# JD_BopIt_Schematic.net
KiCad netlist of a schematic drawn in Altium Designer
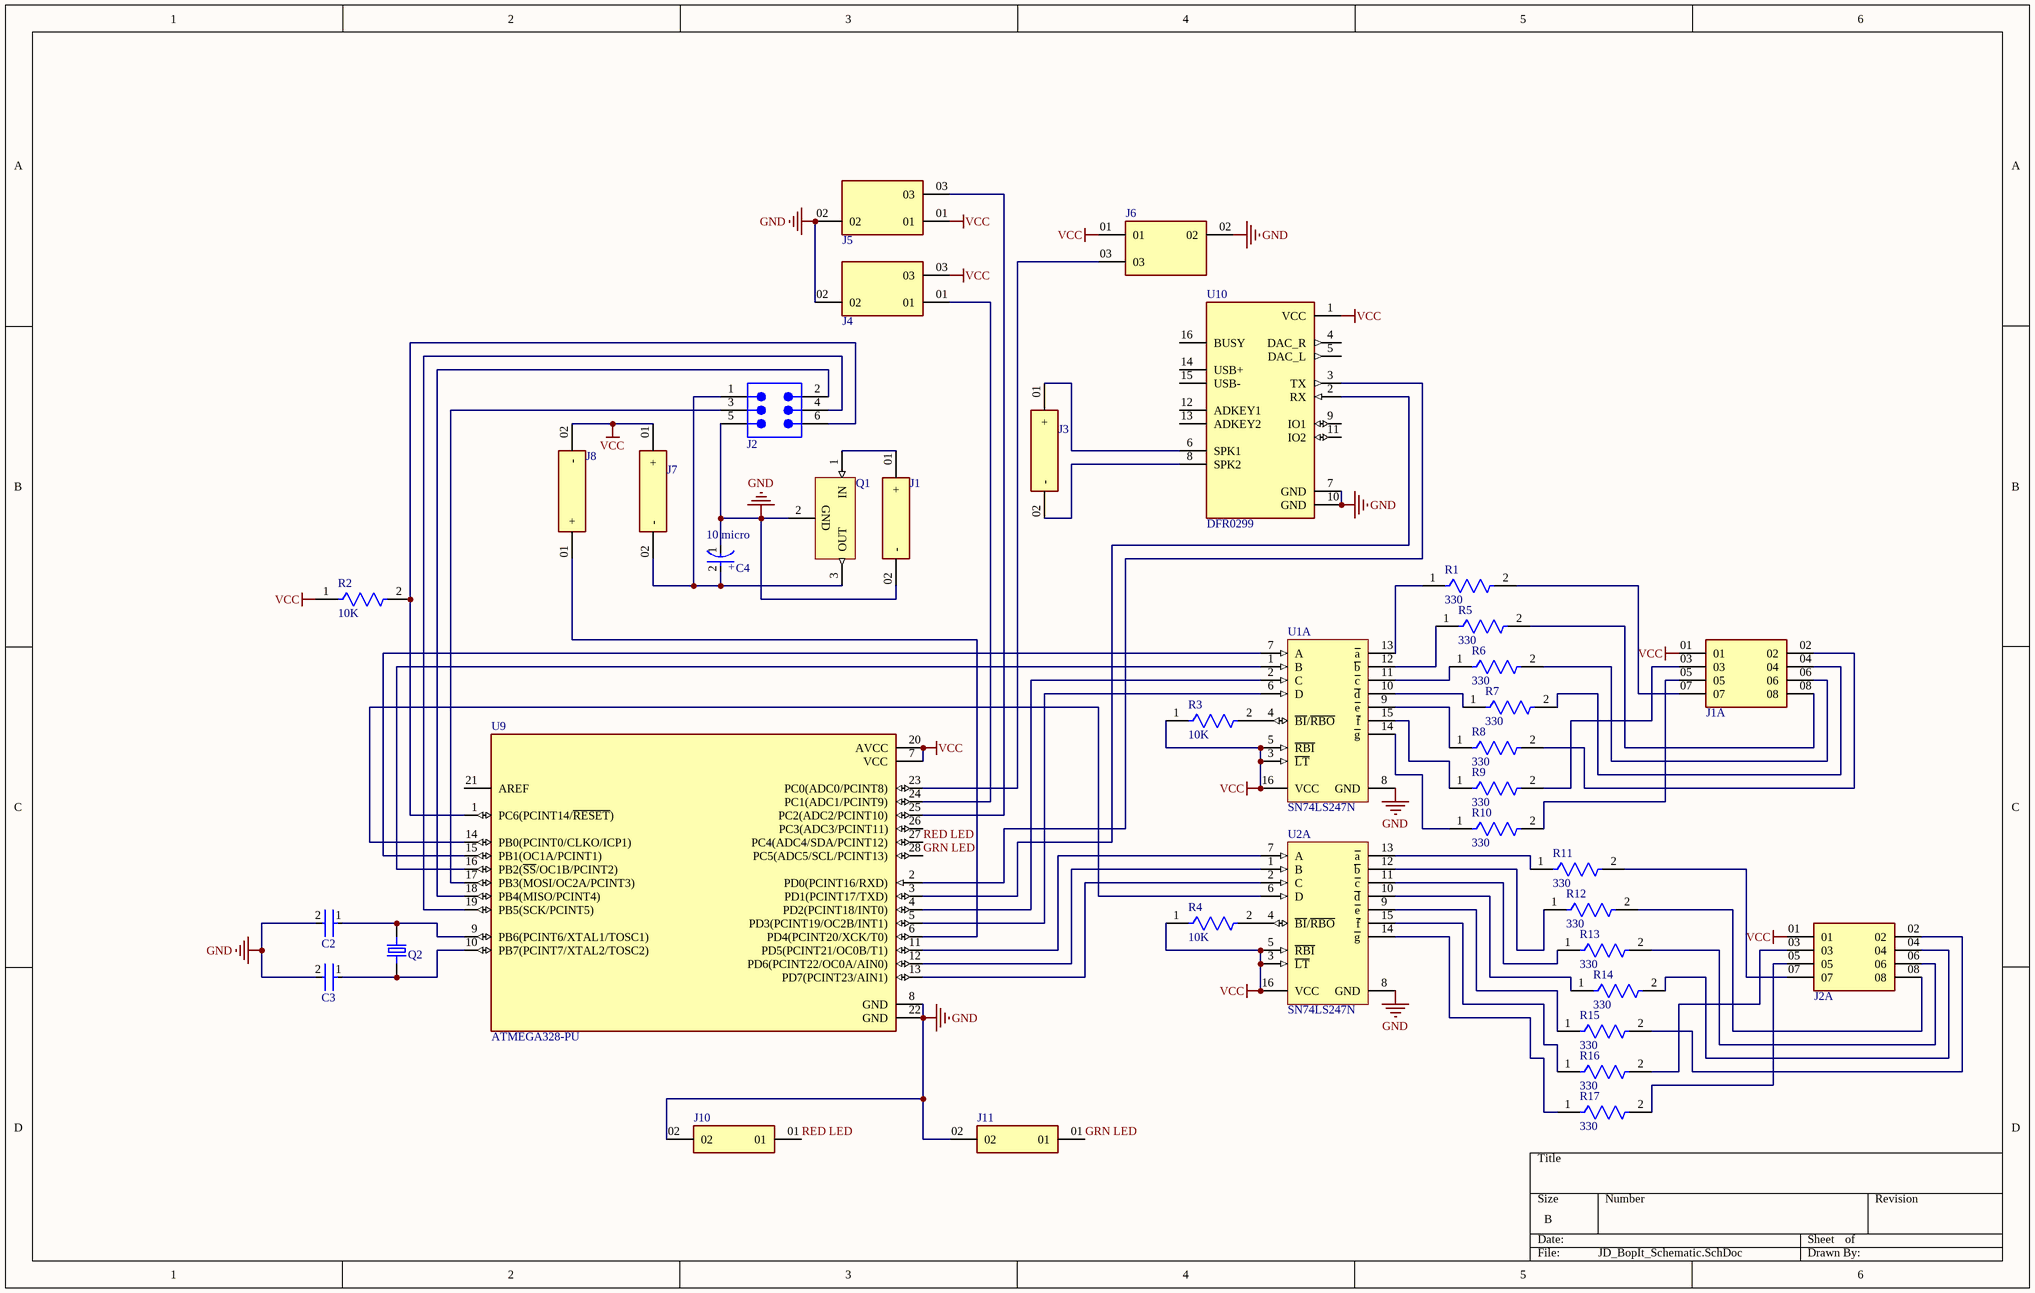
[diagram p0: JD_BopIt_Schematic.SchDoc]

(export (version "E")
  (design (tool "Eeschema 10.0.6"))
  (components
    (comp (ref "C2")
      (value "RCE5C2A220J0DBH03A")
      (footprint "FP-RCE0DB-MFG")
      (description "Cap Ceramic 22pF 100V C0G ±5% Radial 2.5mm +125°C Ammo Pack")
      (fields (field (name "VOLTAGE") "100V") (field (name "TOLERANCE") "5%"))
      (libsource (lib "Altium Content Vault") (part "b4654b650e69147ec39a6b967a45e02"))
    )
    (comp (ref "C3")
      (value "RCE5C2A220J0DBH03A")
      (footprint "FP-RCE0DB-MFG")
      (description "Cap Ceramic 22pF 100V C0G ±5% Radial 2.5mm +125°C Ammo Pack")
      (fields (field (name "VOLTAGE") "100V") (field (name "TOLERANCE") "5%"))
      (libsource (lib "Altium Content Vault") (part "b4654b650e69147ec39a6b967a45e02"))
    )
    (comp (ref "C4")
      (value "10 micro")
      (footprint "FP-173DW-MFG")
      (description "173D106X9025WWE3 173D Series 10 uF ±10% 25 V Axial Solid Electrolyte Tantalum Capacitor")
      (fields (field (name "TOLERANCE") "10%"))
      (libsource (lib "Altium Content Vault") (part "203bc49f2ac43e59fd269a8c329ed05"))
    )
    (comp (ref "J1")
      (value "MTSW-101-09-T-D-231-LL")
      (footprint "SAMTEC_MTSW-101-09-T-D-231-LL")
      (libsource (lib "MTSW-101-09-T-D-231-LL") (part "MTSW-101-09-T-D-231-LL"))
    )
    (comp (ref "J1A")
      (value "TSW-104-09-L-D")
      (footprint "SAMTEC_TSW-104-09-L-D")
      (libsource (lib "TSW-104-09-L-D") (part "TSW-104-09-L-D"))
    )
    (comp (ref "J2")
      (value "61200621621")
      (footprint "61200621621")
      (description "WR-BHD Male Box Header, THT Straight, pitch 2.54mm, 2 row, 6 pin")
      (fields (field (name "MANUFACTURER") "Wurth Elektronik"))
      (libsource (lib "Altium_WR-BHD_rev23a") (part "61200621621"))
    )
    (comp (ref "J2A")
      (value "TSW-104-09-L-D")
      (footprint "SAMTEC_TSW-104-09-L-D")
      (libsource (lib "TSW-104-09-L-D") (part "TSW-104-09-L-D"))
    )
    (comp (ref "J3")
      (value "MTSW-101-09-T-D-231-LL")
      (footprint "SAMTEC_MTSW-101-09-T-D-231-LL")
      (libsource (lib "MTSW-101-09-T-D-231-LL") (part "MTSW-101-09-T-D-231-LL"))
    )
    (comp (ref "J4")
      (value "HTSW-101-07-S-T")
      (footprint "SAMTEC_HTSW-101-07-S-T")
      (description "Connector Header Through Hole 3 position")
      (fields (field (name "MF") "Samtec"))
      (libsource (lib "HTSW-101-07-S-T") (part "HTSW-101-07-S-T"))
    )
    (comp (ref "J5")
      (value "HTSW-101-07-S-T")
      (footprint "SAMTEC_HTSW-101-07-S-T")
      (description "Connector Header Through Hole 3 position")
      (fields (field (name "MF") "Samtec"))
      (libsource (lib "HTSW-101-07-S-T") (part "HTSW-101-07-S-T"))
    )
    (comp (ref "J6")
      (value "HTSW-101-07-S-T")
      (footprint "SAMTEC_HTSW-101-07-S-T")
      (description "Connector Header Through Hole 3 position")
      (fields (field (name "MF") "Samtec"))
      (libsource (lib "") (part "HTSW-101-07-S-T_1"))
    )
    (comp (ref "J7")
      (value "MTSW-101-09-T-D-231-LL")
      (footprint "SAMTEC_MTSW-101-09-T-D-231-LL")
      (libsource (lib "MTSW-101-09-T-D-231-LL") (part "MTSW-101-09-T-D-231-LL"))
    )
    (comp (ref "J8")
      (value "MTSW-101-09-T-D-231-LL")
      (footprint "SAMTEC_MTSW-101-09-T-D-231-LL")
      (libsource (lib "") (part "MTSW-101-09-T-D-231-LL_2"))
    )
    (comp (ref "J10")
      (value "MTSW-101-09-T-D-231-LL")
      (footprint "SAMTEC_MTSW-101-09-T-D-231-LL")
      (libsource (lib "") (part "MTSW-101-09-T-D-231-LL_1"))
    )
    (comp (ref "J11")
      (value "MTSW-101-09-T-D-231-LL")
      (footprint "SAMTEC_MTSW-101-09-T-D-231-LL")
      (libsource (lib "") (part "MTSW-101-09-T-D-231-LL_1"))
    )
    (comp (ref "Q1")
      (value "LM7805CT")
      (footprint "FAIR-TO-220-3")
      (description "Positive Voltage Regulator, 5 V, 1 A, -40 to 125 degC, 3-Pin TO-220, RoHS, Tube")
      (fields (field (name "MANUFACTURER") "FairchildSemiconductor"))
      (libsource (lib "Altium Content Vault") (part "FAIR-LM7805CT-TO220-3"))
    )
    (comp (ref "Q2")
      (value "ECS-160-S-4")
      (footprint "XTAL_ECS-160-20-4X")
      (description "16 MHz Â±30ppm Crystal Series 40 Ohms HC-49/US")
      (fields (field (name "MF") "ECS Inc."))
      (libsource (lib "ECS-160-S-4") (part "ECS-160-S-4"))
    )
    (comp (ref "R1")
      (value "330")
      (footprint "FP-MBB0207-MFG")
      (description "RES 10K OHM 0.6W 1% AXIAL")
      (fields (field (name "TOLERANCE") "1%"))
      (libsource (lib "Altium Content Vault") (part "1029c3af85768c4190bb7ad29bc67b5"))
    )
    (comp (ref "R2")
      (value "10K")
      (footprint "FP-MBB0207-MFG")
      (description "RES 10K OHM 0.6W 1% AXIAL")
      (fields (field (name "TOLERANCE") "1%"))
      (libsource (lib "Altium Content Vault") (part "1029c3af85768c4190bb7ad29bc67b5"))
    )
    (comp (ref "R3")
      (value "10K")
      (footprint "FP-MBB0207-MFG")
      (description "RES 10K OHM 0.6W 1% AXIAL")
      (fields (field (name "TOLERANCE") "1%"))
      (libsource (lib "Altium Content Vault") (part "1029c3af85768c4190bb7ad29bc67b5"))
    )
    (comp (ref "R4")
      (value "10K")
      (footprint "FP-MBB0207-MFG")
      (description "RES 10K OHM 0.6W 1% AXIAL")
      (fields (field (name "TOLERANCE") "1%"))
      (libsource (lib "Altium Content Vault") (part "1029c3af85768c4190bb7ad29bc67b5"))
    )
    (comp (ref "R5")
      (value "330")
      (footprint "FP-MBB0207-MFG")
      (description "RES 10K OHM 0.6W 1% AXIAL")
      (fields (field (name "TOLERANCE") "1%"))
      (libsource (lib "Altium Content Vault") (part "1029c3af85768c4190bb7ad29bc67b5"))
    )
    (comp (ref "R6")
      (value "330")
      (footprint "FP-MBB0207-MFG")
      (description "RES 10K OHM 0.6W 1% AXIAL")
      (fields (field (name "TOLERANCE") "1%"))
      (libsource (lib "Altium Content Vault") (part "1029c3af85768c4190bb7ad29bc67b5"))
    )
    (comp (ref "R7")
      (value "330")
      (footprint "FP-MBB0207-MFG")
      (description "RES 10K OHM 0.6W 1% AXIAL")
      (fields (field (name "TOLERANCE") "1%"))
      (libsource (lib "Altium Content Vault") (part "1029c3af85768c4190bb7ad29bc67b5"))
    )
    (comp (ref "R8")
      (value "330")
      (footprint "FP-MBB0207-MFG")
      (description "RES 10K OHM 0.6W 1% AXIAL")
      (fields (field (name "TOLERANCE") "1%"))
      (libsource (lib "Altium Content Vault") (part "1029c3af85768c4190bb7ad29bc67b5"))
    )
    (comp (ref "R9")
      (value "330")
      (footprint "FP-MBB0207-MFG")
      (description "RES 10K OHM 0.6W 1% AXIAL")
      (fields (field (name "TOLERANCE") "1%"))
      (libsource (lib "Altium Content Vault") (part "1029c3af85768c4190bb7ad29bc67b5"))
    )
    (comp (ref "R10")
      (value "330")
      (footprint "FP-MBB0207-MFG")
      (description "RES 10K OHM 0.6W 1% AXIAL")
      (fields (field (name "TOLERANCE") "1%"))
      (libsource (lib "Altium Content Vault") (part "1029c3af85768c4190bb7ad29bc67b5"))
    )
    (comp (ref "R11")
      (value "330")
      (footprint "FP-MBB0207-MFG")
      (description "RES 10K OHM 0.6W 1% AXIAL")
      (fields (field (name "TOLERANCE") "1%"))
      (libsource (lib "Altium Content Vault") (part "1029c3af85768c4190bb7ad29bc67b5"))
    )
    (comp (ref "R12")
      (value "330")
      (footprint "FP-MBB0207-MFG")
      (description "RES 10K OHM 0.6W 1% AXIAL")
      (fields (field (name "TOLERANCE") "1%"))
      (libsource (lib "Altium Content Vault") (part "1029c3af85768c4190bb7ad29bc67b5"))
    )
    (comp (ref "R13")
      (value "330")
      (footprint "FP-MBB0207-MFG")
      (description "RES 10K OHM 0.6W 1% AXIAL")
      (fields (field (name "TOLERANCE") "1%"))
      (libsource (lib "Altium Content Vault") (part "1029c3af85768c4190bb7ad29bc67b5"))
    )
    (comp (ref "R14")
      (value "330")
      (footprint "FP-MBB0207-MFG")
      (description "RES 10K OHM 0.6W 1% AXIAL")
      (fields (field (name "TOLERANCE") "1%"))
      (libsource (lib "Altium Content Vault") (part "1029c3af85768c4190bb7ad29bc67b5"))
    )
    (comp (ref "R15")
      (value "330")
      (footprint "FP-MBB0207-MFG")
      (description "RES 10K OHM 0.6W 1% AXIAL")
      (fields (field (name "TOLERANCE") "1%"))
      (libsource (lib "Altium Content Vault") (part "1029c3af85768c4190bb7ad29bc67b5"))
    )
    (comp (ref "R16")
      (value "330")
      (footprint "FP-MBB0207-MFG")
      (description "RES 10K OHM 0.6W 1% AXIAL")
      (fields (field (name "TOLERANCE") "1%"))
      (libsource (lib "Altium Content Vault") (part "1029c3af85768c4190bb7ad29bc67b5"))
    )
    (comp (ref "R17")
      (value "330")
      (footprint "FP-MBB0207-MFG")
      (description "RES 10K OHM 0.6W 1% AXIAL")
      (fields (field (name "TOLERANCE") "1%"))
      (libsource (lib "Altium Content Vault") (part "1029c3af85768c4190bb7ad29bc67b5"))
    )
    (comp (ref "U1A")
      (value "SN74LS247N")
      (footprint "N0016A")
      (description "BCD-to-7-Segment Decoder / Driver, 4.75 to 5.25 V, 0 to 70 degC, 16-pin DIP (N16), Pb-Free (RoHS)")
      (fields (field (name "MANUFACTURER") "Texas Instruments"))
      (libsource (lib "Altium Content Vault") (part "TI-SNX4XX247-16"))
    )
    (comp (ref "U2A")
      (value "SN74LS247N")
      (footprint "N0016A")
      (description "BCD-to-7-Segment Decoder / Driver, 4.75 to 5.25 V, 0 to 70 degC, 16-pin DIP (N16), Pb-Free (RoHS)")
      (fields (field (name "MANUFACTURER") "Texas Instruments"))
      (libsource (lib "Altium Content Vault") (part "TI-SNX4XX247-16"))
    )
    (comp (ref "U9")
      (value "ATMEGA328-PU")
      (footprint "DIP787W46P254L3467H508Q28")
      (description "AVR AVRÂ® ATmega Microcontroller IC 8-Bit 20MHz 32KB (16K x 16) FLASH 28-PDIP")
      (fields (field (name "MF") "Microchip"))
      (libsource (lib "ATMEGA328-PU") (part "ATMEGA328-PU"))
    )
    (comp (ref "U10")
      (value "DFR0299")
      (footprint "MODULE_DFR0299")
      (description "- MP3 Player Audio Arduino Platform Evaluation Expansion Board")
      (fields (field (name "MF") "DFRobot"))
      (libsource (lib "DFR0299") (part "DFR0299"))
    )
  )
  (nets
    (net (code "1") (name "/GRN LED") (class "Default")
      (node (ref "J11") (pin "01") (pinfunction "01_01") (pintype "passive"))
      (node (ref "U9") (pin "28") (pinfunction "PC5(ADC5/SCL/PCINT13)_28") (pintype "bidirectional"))
    )
    (net (code "2") (name "/RED LED") (class "Default")
      (node (ref "J10") (pin "01") (pinfunction "01_01") (pintype "passive"))
      (node (ref "U9") (pin "27") (pinfunction "PC4(ADC4/SDA/PCINT12)_27") (pintype "bidirectional"))
    )
    (net (code "3") (name "GND") (class "Default")
      (node (ref "C2") (pin "2") (pinfunction "2_2") (pintype "passive"))
      (node (ref "C3") (pin "2") (pinfunction "2_2") (pintype "passive"))
      (node (ref "C4") (pin "1") (pinfunction "C_1") (pintype "passive"))
      (node (ref "J1") (pin "02") (pinfunction "-_02") (pintype "passive"))
      (node (ref "J10") (pin "02") (pinfunction "02_02") (pintype "passive"))
      (node (ref "J11") (pin "02") (pinfunction "02_02") (pintype "passive"))
      (node (ref "J2") (pin "5") (pinfunction "5_5") (pintype "passive"))
      (node (ref "J4") (pin "02") (pinfunction "02_02") (pintype "passive"))
      (node (ref "J5") (pin "02") (pinfunction "02_02") (pintype "passive"))
      (node (ref "J6") (pin "02") (pinfunction "02_02") (pintype "passive"))
      (node (ref "Q1") (pin "2") (pinfunction "GND_2") (pintype "power_in"))
      (node (ref "U10") (pin "10") (pinfunction "GND_10") (pintype "power_in"))
      (node (ref "U10") (pin "7") (pinfunction "GND_7") (pintype "power_in"))
      (node (ref "U1A") (pin "8") (pinfunction "GND_8") (pintype "power_in"))
      (node (ref "U2A") (pin "8") (pinfunction "GND_8") (pintype "power_in"))
      (node (ref "U9") (pin "22") (pinfunction "GND_22") (pintype "power_in"))
      (node (ref "U9") (pin "8") (pinfunction "GND_8") (pintype "power_in"))
    )
    (net (code "4") (name "Net-(C4-A)") (class "Default")
      (node (ref "C4") (pin "2") (pinfunction "A_2") (pintype "passive"))
      (node (ref "J2") (pin "1") (pinfunction "1_1") (pintype "passive"))
      (node (ref "J7") (pin "02") (pinfunction "-_02") (pintype "passive"))
      (node (ref "Q1") (pin "3") (pinfunction "OUT_3") (pintype "output"))
    )
    (net (code "5") (name "Net-(J1-+)") (class "Default")
      (node (ref "J1") (pin "01") (pinfunction "+_01") (pintype "passive"))
      (node (ref "Q1") (pin "1") (pinfunction "IN_1") (pintype "input"))
    )
    (net (code "6") (name "Net-(J1A-Pad02)") (class "Default")
      (node (ref "J1A") (pin "02") (pinfunction "02_02") (pintype "passive"))
      (node (ref "R8") (pin "2") (pinfunction "2_2") (pintype "passive"))
    )
    (net (code "7") (name "Net-(J1A-Pad03)") (class "Default")
      (node (ref "J1A") (pin "03") (pinfunction "03_03") (pintype "passive"))
      (node (ref "R9") (pin "2") (pinfunction "2_2") (pintype "passive"))
    )
    (net (code "8") (name "Net-(J1A-Pad04)") (class "Default")
      (node (ref "J1A") (pin "04") (pinfunction "04_04") (pintype "passive"))
      (node (ref "R7") (pin "2") (pinfunction "2_2") (pintype "passive"))
    )
    (net (code "9") (name "Net-(J1A-Pad05)") (class "Default")
      (node (ref "J1A") (pin "05") (pinfunction "05_05") (pintype "passive"))
      (node (ref "R10") (pin "2") (pinfunction "2_2") (pintype "passive"))
    )
    (net (code "10") (name "Net-(J1A-Pad06)") (class "Default")
      (node (ref "J1A") (pin "06") (pinfunction "06_06") (pintype "passive"))
      (node (ref "R6") (pin "2") (pinfunction "2_2") (pintype "passive"))
    )
    (net (code "11") (name "Net-(J1A-Pad07)") (class "Default")
      (node (ref "J1A") (pin "07") (pinfunction "07_07") (pintype "passive"))
      (node (ref "R1") (pin "2") (pinfunction "2_2") (pintype "passive"))
    )
    (net (code "12") (name "Net-(J1A-Pad08)") (class "Default")
      (node (ref "J1A") (pin "08") (pinfunction "08_08") (pintype "passive"))
      (node (ref "R5") (pin "2") (pinfunction "2_2") (pintype "passive"))
    )
    (net (code "13") (name "Net-(J2A-Pad02)") (class "Default")
      (node (ref "J2A") (pin "02") (pinfunction "02_02") (pintype "passive"))
      (node (ref "R15") (pin "2") (pinfunction "2_2") (pintype "passive"))
    )
    (net (code "14") (name "Net-(J2A-Pad03)") (class "Default")
      (node (ref "J2A") (pin "03") (pinfunction "03_03") (pintype "passive"))
      (node (ref "R16") (pin "2") (pinfunction "2_2") (pintype "passive"))
    )
    (net (code "15") (name "Net-(J2A-Pad04)") (class "Default")
      (node (ref "J2A") (pin "04") (pinfunction "04_04") (pintype "passive"))
      (node (ref "R14") (pin "2") (pinfunction "2_2") (pintype "passive"))
    )
    (net (code "16") (name "Net-(J2A-Pad05)") (class "Default")
      (node (ref "J2A") (pin "05") (pinfunction "05_05") (pintype "passive"))
      (node (ref "R17") (pin "2") (pinfunction "2_2") (pintype "passive"))
    )
    (net (code "17") (name "Net-(J2A-Pad06)") (class "Default")
      (node (ref "J2A") (pin "06") (pinfunction "06_06") (pintype "passive"))
      (node (ref "R13") (pin "2") (pinfunction "2_2") (pintype "passive"))
    )
    (net (code "18") (name "Net-(J2A-Pad07)") (class "Default")
      (node (ref "J2A") (pin "07") (pinfunction "07_07") (pintype "passive"))
      (node (ref "R11") (pin "2") (pinfunction "2_2") (pintype "passive"))
    )
    (net (code "19") (name "Net-(J2A-Pad08)") (class "Default")
      (node (ref "J2A") (pin "08") (pinfunction "08_08") (pintype "passive"))
      (node (ref "R12") (pin "2") (pinfunction "2_2") (pintype "passive"))
    )
    (net (code "20") (name "Net-(J3-+)") (class "Default")
      (node (ref "J3") (pin "01") (pinfunction "+_01") (pintype "passive"))
      (node (ref "U10") (pin "6") (pinfunction "SPK1_6") (pintype "passive"))
    )
    (net (code "21") (name "Net-(J3--)") (class "Default")
      (node (ref "J3") (pin "02") (pinfunction "-_02") (pintype "passive"))
      (node (ref "U10") (pin "8") (pinfunction "SPK2_8") (pintype "passive"))
    )
    (net (code "22") (name "Net-(J8-+)") (class "Default")
      (node (ref "J8") (pin "01") (pinfunction "+_01") (pintype "passive"))
      (node (ref "U9") (pin "6") (pinfunction "PD4(PCINT20/XCK/T0)_6") (pintype "bidirectional"))
    )
    (net (code "23") (name "Net-(U1A-A)") (class "Default")
      (node (ref "U1A") (pin "7") (pinfunction "A_7") (pintype "input"))
      (node (ref "U9") (pin "15") (pinfunction "PB1(OC1A/PCINT1)_15") (pintype "bidirectional"))
    )
    (net (code "24") (name "Net-(U1A-B)") (class "Default")
      (node (ref "U1A") (pin "1") (pinfunction "B_1") (pintype "input"))
      (node (ref "U9") (pin "16") (pinfunction "PB2(~{SS}/OC1B/PCINT2)_16") (pintype "bidirectional"))
    )
    (net (code "25") (name "Net-(U1A-C)") (class "Default")
      (node (ref "U1A") (pin "2") (pinfunction "C_2") (pintype "input"))
      (node (ref "U9") (pin "4") (pinfunction "PD2(PCINT18/INT0)_4") (pintype "bidirectional"))
    )
    (net (code "26") (name "Net-(U1A-D)") (class "Default")
      (node (ref "U1A") (pin "6") (pinfunction "D_6") (pintype "input"))
      (node (ref "U9") (pin "5") (pinfunction "PD3(PCINT19/OC2B/INT1)_5") (pintype "bidirectional"))
    )
    (net (code "27") (name "Net-(U1A-~{BI}{slash}~{RBO})") (class "Default")
      (node (ref "R3") (pin "2") (pinfunction "2_2") (pintype "passive"))
      (node (ref "U1A") (pin "4") (pinfunction "~{BI}/~{RBO}_4") (pintype "bidirectional"))
    )
    (net (code "28") (name "Net-(U1A-~{a})") (class "Default")
      (node (ref "R1") (pin "1") (pinfunction "1_1") (pintype "passive"))
      (node (ref "U1A") (pin "13") (pinfunction "~{a}_13") (pintype "open_collector"))
    )
    (net (code "29") (name "Net-(U1A-~{b})") (class "Default")
      (node (ref "R5") (pin "1") (pinfunction "1_1") (pintype "passive"))
      (node (ref "U1A") (pin "12") (pinfunction "~{b}_12") (pintype "open_collector"))
    )
    (net (code "30") (name "Net-(U1A-~{c})") (class "Default")
      (node (ref "R6") (pin "1") (pinfunction "1_1") (pintype "passive"))
      (node (ref "U1A") (pin "11") (pinfunction "~{c}_11") (pintype "open_collector"))
    )
    (net (code "31") (name "Net-(U1A-~{d})") (class "Default")
      (node (ref "R7") (pin "1") (pinfunction "1_1") (pintype "passive"))
      (node (ref "U1A") (pin "10") (pinfunction "~{d}_10") (pintype "open_collector"))
    )
    (net (code "32") (name "Net-(U1A-~{e})") (class "Default")
      (node (ref "R8") (pin "1") (pinfunction "1_1") (pintype "passive"))
      (node (ref "U1A") (pin "9") (pinfunction "~{e}_9") (pintype "open_collector"))
    )
    (net (code "33") (name "Net-(U1A-~{f})") (class "Default")
      (node (ref "R9") (pin "1") (pinfunction "1_1") (pintype "passive"))
      (node (ref "U1A") (pin "15") (pinfunction "~{f}_15") (pintype "open_collector"))
    )
    (net (code "34") (name "Net-(U1A-~{g})") (class "Default")
      (node (ref "R10") (pin "1") (pinfunction "1_1") (pintype "passive"))
      (node (ref "U1A") (pin "14") (pinfunction "~{g}_14") (pintype "open_collector"))
    )
    (net (code "35") (name "Net-(U2A-A)") (class "Default")
      (node (ref "U2A") (pin "7") (pinfunction "A_7") (pintype "input"))
      (node (ref "U9") (pin "11") (pinfunction "PD5(PCINT21/OC0B/T1)_11") (pintype "bidirectional"))
    )
    (net (code "36") (name "Net-(U2A-B)") (class "Default")
      (node (ref "U2A") (pin "1") (pinfunction "B_1") (pintype "input"))
      (node (ref "U9") (pin "12") (pinfunction "PD6(PCINT22/OC0A/AIN0)_12") (pintype "bidirectional"))
    )
    (net (code "37") (name "Net-(U2A-C)") (class "Default")
      (node (ref "U2A") (pin "2") (pinfunction "C_2") (pintype "input"))
      (node (ref "U9") (pin "13") (pinfunction "PD7(PCINT23/AIN1)_13") (pintype "bidirectional"))
    )
    (net (code "38") (name "Net-(U2A-D)") (class "Default")
      (node (ref "U2A") (pin "6") (pinfunction "D_6") (pintype "input"))
      (node (ref "U9") (pin "14") (pinfunction "PB0(PCINT0/CLKO/ICP1)_14") (pintype "bidirectional"))
    )
    (net (code "39") (name "Net-(U2A-~{BI}{slash}~{RBO})") (class "Default")
      (node (ref "R4") (pin "2") (pinfunction "2_2") (pintype "passive"))
      (node (ref "U2A") (pin "4") (pinfunction "~{BI}/~{RBO}_4") (pintype "bidirectional"))
    )
    (net (code "40") (name "Net-(U2A-~{a})") (class "Default")
      (node (ref "R11") (pin "1") (pinfunction "1_1") (pintype "passive"))
      (node (ref "U2A") (pin "13") (pinfunction "~{a}_13") (pintype "open_collector"))
    )
    (net (code "41") (name "Net-(U2A-~{b})") (class "Default")
      (node (ref "R12") (pin "1") (pinfunction "1_1") (pintype "passive"))
      (node (ref "U2A") (pin "12") (pinfunction "~{b}_12") (pintype "open_collector"))
    )
    (net (code "42") (name "Net-(U2A-~{c})") (class "Default")
      (node (ref "R13") (pin "1") (pinfunction "1_1") (pintype "passive"))
      (node (ref "U2A") (pin "11") (pinfunction "~{c}_11") (pintype "open_collector"))
    )
    (net (code "43") (name "Net-(U2A-~{d})") (class "Default")
      (node (ref "R14") (pin "1") (pinfunction "1_1") (pintype "passive"))
      (node (ref "U2A") (pin "10") (pinfunction "~{d}_10") (pintype "open_collector"))
    )
    (net (code "44") (name "Net-(U2A-~{e})") (class "Default")
      (node (ref "R15") (pin "1") (pinfunction "1_1") (pintype "passive"))
      (node (ref "U2A") (pin "9") (pinfunction "~{e}_9") (pintype "open_collector"))
    )
    (net (code "45") (name "Net-(U2A-~{f})") (class "Default")
      (node (ref "R16") (pin "1") (pinfunction "1_1") (pintype "passive"))
      (node (ref "U2A") (pin "15") (pinfunction "~{f}_15") (pintype "open_collector"))
    )
    (net (code "46") (name "Net-(U2A-~{g})") (class "Default")
      (node (ref "R17") (pin "1") (pinfunction "1_1") (pintype "passive"))
      (node (ref "U2A") (pin "14") (pinfunction "~{g}_14") (pintype "open_collector"))
    )
    (net (code "47") (name "Net-(U9-PB3(MOSI{slash}OC2A{slash}PCINT3))") (class "Default")
      (node (ref "J2") (pin "3") (pinfunction "3_3") (pintype "passive"))
      (node (ref "U9") (pin "17") (pinfunction "PB3(MOSI/OC2A/PCINT3)_17") (pintype "bidirectional"))
    )
    (net (code "48") (name "Net-(U9-PB4(MISO{slash}PCINT4))") (class "Default")
      (node (ref "J2") (pin "2") (pinfunction "2_2") (pintype "passive"))
      (node (ref "U9") (pin "18") (pinfunction "PB4(MISO/PCINT4)_18") (pintype "bidirectional"))
    )
    (net (code "49") (name "Net-(U9-PB5(SCK{slash}PCINT5))") (class "Default")
      (node (ref "J2") (pin "4") (pinfunction "4_4") (pintype "passive"))
      (node (ref "U9") (pin "19") (pinfunction "PB5(SCK/PCINT5)_19") (pintype "bidirectional"))
    )
    (net (code "50") (name "Net-(U9-PB6(PCINT6{slash}XTAL1{slash}TOSC1))") (class "Default")
      (node (ref "C2") (pin "1") (pinfunction "1_1") (pintype "passive"))
      (node (ref "Q2") (pin "2") (pinfunction "2_2") (pintype "passive"))
      (node (ref "U9") (pin "9") (pinfunction "PB6(PCINT6/XTAL1/TOSC1)_9") (pintype "bidirectional"))
    )
    (net (code "51") (name "Net-(U9-PB7(PCINT7{slash}XTAL2{slash}TOSC2))") (class "Default")
      (node (ref "C3") (pin "1") (pinfunction "1_1") (pintype "passive"))
      (node (ref "Q2") (pin "1") (pinfunction "1_1") (pintype "passive"))
      (node (ref "U9") (pin "10") (pinfunction "PB7(PCINT7/XTAL2/TOSC2)_10") (pintype "bidirectional"))
    )
    (net (code "52") (name "Net-(U9-PC0(ADC0{slash}PCINT8))") (class "Default")
      (node (ref "J6") (pin "03") (pinfunction "03_03") (pintype "passive"))
      (node (ref "U9") (pin "23") (pinfunction "PC0(ADC0/PCINT8)_23") (pintype "bidirectional"))
    )
    (net (code "53") (name "Net-(U9-PC1(ADC1{slash}PCINT9))") (class "Default")
      (node (ref "J4") (pin "01") (pinfunction "01_01") (pintype "passive"))
      (node (ref "U9") (pin "24") (pinfunction "PC1(ADC1/PCINT9)_24") (pintype "bidirectional"))
    )
    (net (code "54") (name "Net-(U9-PC2(ADC2{slash}PCINT10))") (class "Default")
      (node (ref "J5") (pin "03") (pinfunction "03_03") (pintype "passive"))
      (node (ref "U9") (pin "25") (pinfunction "PC2(ADC2/PCINT10)_25") (pintype "bidirectional"))
    )
    (net (code "55") (name "Net-(U9-PC6(PCINT14{slash}~{RESET}))") (class "Default")
      (node (ref "J2") (pin "6") (pinfunction "6_6") (pintype "passive"))
      (node (ref "R2") (pin "2") (pinfunction "2_2") (pintype "passive"))
      (node (ref "U9") (pin "1") (pinfunction "PC6(PCINT14/~{RESET})_1") (pintype "bidirectional"))
    )
    (net (code "56") (name "Net-(U10-RX)") (class "Default")
      (node (ref "U10") (pin "2") (pinfunction "RX_2") (pintype "input"))
      (node (ref "U9") (pin "3") (pinfunction "PD1(PCINT17/TXD)_3") (pintype "bidirectional"))
    )
    (net (code "57") (name "Net-(U10-TX)") (class "Default")
      (node (ref "U10") (pin "3") (pinfunction "TX_3") (pintype "output"))
      (node (ref "U9") (pin "2") (pinfunction "PD0(PCINT16/RXD)_2") (pintype "input"))
    )
    (net (code "58") (name "VCC") (class "Default")
      (node (ref "J1A") (pin "01") (pinfunction "01_01") (pintype "passive"))
      (node (ref "J2A") (pin "01") (pinfunction "01_01") (pintype "passive"))
      (node (ref "J4") (pin "03") (pinfunction "03_03") (pintype "passive"))
      (node (ref "J5") (pin "01") (pinfunction "01_01") (pintype "passive"))
      (node (ref "J6") (pin "01") (pinfunction "01_01") (pintype "passive"))
      (node (ref "J7") (pin "01") (pinfunction "+_01") (pintype "passive"))
      (node (ref "J8") (pin "02") (pinfunction "-_02") (pintype "passive"))
      (node (ref "R2") (pin "1") (pinfunction "1_1") (pintype "passive"))
      (node (ref "R3") (pin "1") (pinfunction "1_1") (pintype "passive"))
      (node (ref "R4") (pin "1") (pinfunction "1_1") (pintype "passive"))
      (node (ref "U10") (pin "1") (pinfunction "VCC_1") (pintype "power_in"))
      (node (ref "U1A") (pin "16") (pinfunction "VCC_16") (pintype "power_in"))
      (node (ref "U1A") (pin "3") (pinfunction "~{LT}_3") (pintype "input"))
      (node (ref "U1A") (pin "5") (pinfunction "~{RBI}_5") (pintype "input"))
      (node (ref "U2A") (pin "16") (pinfunction "VCC_16") (pintype "power_in"))
      (node (ref "U2A") (pin "3") (pinfunction "~{LT}_3") (pintype "input"))
      (node (ref "U2A") (pin "5") (pinfunction "~{RBI}_5") (pintype "input"))
      (node (ref "U9") (pin "20") (pinfunction "AVCC_20") (pintype "power_in"))
      (node (ref "U9") (pin "7") (pinfunction "VCC_7") (pintype "power_in"))
    )
    (net (code "59") (name "unconnected-(U9-AREF-Pad21)") (class "Default")
      (node (ref "U9") (pin "21") (pinfunction "AREF_21") (pintype "passive"))
    )
    (net (code "60") (name "unconnected-(U9-PC3(ADC3{slash}PCINT11)-Pad26)") (class "Default")
      (node (ref "U9") (pin "26") (pinfunction "PC3(ADC3/PCINT11)_26") (pintype "bidirectional"))
    )
    (net (code "61") (name "unconnected-(U10-ADKEY1-Pad12)") (class "Default")
      (node (ref "U10") (pin "12") (pinfunction "ADKEY1_12") (pintype "passive"))
    )
    (net (code "62") (name "unconnected-(U10-ADKEY2-Pad13)") (class "Default")
      (node (ref "U10") (pin "13") (pinfunction "ADKEY2_13") (pintype "passive"))
    )
    (net (code "63") (name "unconnected-(U10-BUSY-Pad16)") (class "Default")
      (node (ref "U10") (pin "16") (pinfunction "BUSY_16") (pintype "passive"))
    )
    (net (code "64") (name "unconnected-(U10-DAC_L-Pad5)") (class "Default")
      (node (ref "U10") (pin "5") (pinfunction "DAC_L_5") (pintype "output"))
    )
    (net (code "65") (name "unconnected-(U10-DAC_R-Pad4)") (class "Default")
      (node (ref "U10") (pin "4") (pinfunction "DAC_R_4") (pintype "output"))
    )
    (net (code "66") (name "unconnected-(U10-IO1-Pad9)") (class "Default")
      (node (ref "U10") (pin "9") (pinfunction "IO1_9") (pintype "bidirectional"))
    )
    (net (code "67") (name "unconnected-(U10-IO2-Pad11)") (class "Default")
      (node (ref "U10") (pin "11") (pinfunction "IO2_11") (pintype "bidirectional"))
    )
    (net (code "68") (name "unconnected-(U10-USB+-Pad14)") (class "Default")
      (node (ref "U10") (pin "14") (pinfunction "USB+_14") (pintype "passive"))
    )
    (net (code "69") (name "unconnected-(U10-USB--Pad15)") (class "Default")
      (node (ref "U10") (pin "15") (pinfunction "USB-_15") (pintype "passive"))
    )
  )
)
